# G772B.net
KiCad netlist of a schematic drawn in EAGLE
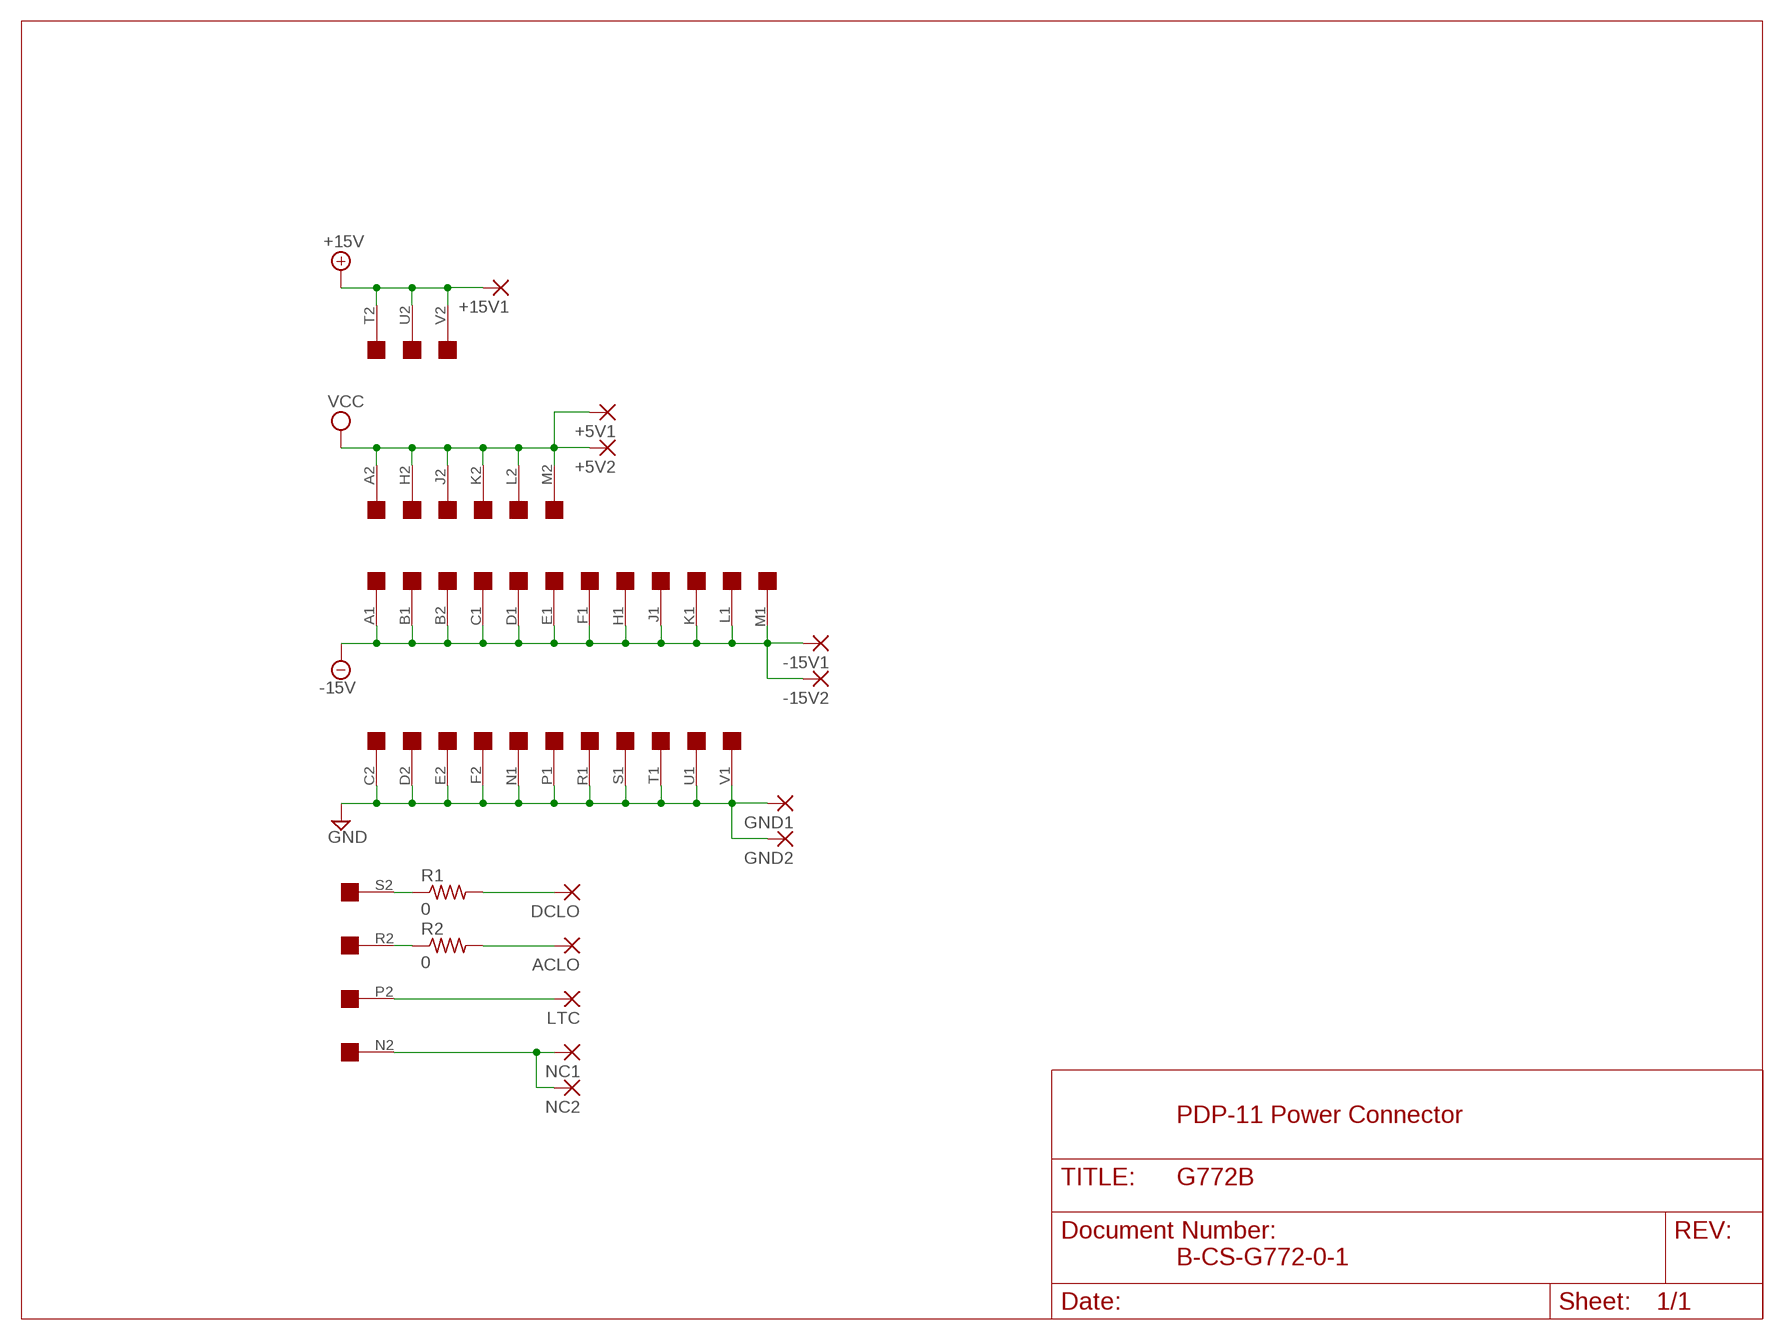
[diagram p0: schematic, sheet 1]

(export (version "E")
  (design (tool "Eeschema 10.0.6"))
  (components
    (comp (ref "+5V1")
      (value "2,54/1,0")
      (footprint "eagle-import:2,54_1,0")
      (libsource (lib "eagle-import") (part "2,54/1,0"))
    )
    (comp (ref "+5V2")
      (value "2,54/1,0")
      (footprint "eagle-import:2,54_1,0")
      (libsource (lib "eagle-import") (part "2,54/1,0"))
    )
    (comp (ref "+15V1")
      (value "2,54/1,0")
      (footprint "eagle-import:2,54_1,0")
      (libsource (lib "eagle-import") (part "2,54/1,0"))
    )
    (comp (ref "-15V1")
      (value "2,54/1,0")
      (footprint "eagle-import:2,54_1,0")
      (libsource (lib "eagle-import") (part "2,54/1,0"))
    )
    (comp (ref "-15V2")
      (value "2,54/1,0")
      (footprint "eagle-import:2,54_1,0")
      (libsource (lib "eagle-import") (part "2,54/1,0"))
    )
    (comp (ref "ACLO")
      (value "2,54/1,0")
      (footprint "eagle-import:2,54_1,0")
      (libsource (lib "eagle-import") (part "2,54/1,0"))
    )
    (comp (ref "DCLO")
      (value "2,54/1,0")
      (footprint "eagle-import:2,54_1,0")
      (libsource (lib "eagle-import") (part "2,54/1,0"))
    )
    (comp (ref "GND1")
      (value "2,54/1,0")
      (footprint "eagle-import:2,54_1,0")
      (libsource (lib "eagle-import") (part "2,54/1,0"))
    )
    (comp (ref "GND2")
      (value "2,54/1,0")
      (footprint "eagle-import:2,54_1,0")
      (libsource (lib "eagle-import") (part "2,54/1,0"))
    )
    (comp (ref "LTC")
      (value "2,54/1,0")
      (footprint "eagle-import:2,54_1,0")
      (libsource (lib "eagle-import") (part "2,54/1,0"))
    )
    (comp (ref "NC1")
      (value "2,54/1,0")
      (footprint "eagle-import:2,54_1,0")
      (libsource (lib "eagle-import") (part "2,54/1,0"))
    )
    (comp (ref "NC2")
      (value "2,54/1,0")
      (footprint "eagle-import:2,54_1,0")
      (libsource (lib "eagle-import") (part "2,54/1,0"))
    )
    (comp (ref "R1")
      (value "0")
      (footprint "eagle-import:0207_10")
      (libsource (lib "eagle-import") (part "R-US_0207/10"))
    )
    (comp (ref "R2")
      (value "0")
      (footprint "eagle-import:0207_10")
      (libsource (lib "eagle-import") (part "R-US_0207/10"))
    )
    (comp (ref "U$1")
      (value "SINGLE")
      (footprint "eagle-import:EDGE-CON2")
      (libsource (lib "eagle-import") (part "SINGLE"))
    )
  )
  (nets
    (net (code "1") (name "+15V") (class "Default")
      (node (ref "+15V1") (pin "1") (pinfunction "P_1") (pintype "passive"))
      (node (ref "U$1") (pin "T2") (pinfunction "1_T2") (pintype "bidirectional"))
      (node (ref "U$1") (pin "U2") (pinfunction "1_U2") (pintype "bidirectional"))
      (node (ref "U$1") (pin "V2") (pinfunction "1_V2") (pintype "bidirectional"))
    )
    (net (code "2") (name "-15V") (class "Default")
      (node (ref "-15V1") (pin "1") (pinfunction "P_1") (pintype "passive"))
      (node (ref "-15V2") (pin "1") (pinfunction "P_1") (pintype "passive"))
      (node (ref "U$1") (pin "A1") (pinfunction "1_A1") (pintype "bidirectional"))
      (node (ref "U$1") (pin "B1") (pinfunction "1_B1") (pintype "bidirectional"))
      (node (ref "U$1") (pin "B2") (pinfunction "1_B2") (pintype "bidirectional"))
      (node (ref "U$1") (pin "C1") (pinfunction "1_C1") (pintype "bidirectional"))
      (node (ref "U$1") (pin "D1") (pinfunction "1_D1") (pintype "bidirectional"))
      (node (ref "U$1") (pin "E1") (pinfunction "1_E1") (pintype "bidirectional"))
      (node (ref "U$1") (pin "F1") (pinfunction "1_F1") (pintype "bidirectional"))
      (node (ref "U$1") (pin "H1") (pinfunction "1_H1") (pintype "bidirectional"))
      (node (ref "U$1") (pin "J1") (pinfunction "1_J1") (pintype "bidirectional"))
      (node (ref "U$1") (pin "K1") (pinfunction "1_K1") (pintype "bidirectional"))
      (node (ref "U$1") (pin "L1") (pinfunction "1_L1") (pintype "bidirectional"))
      (node (ref "U$1") (pin "M1") (pinfunction "1_M1") (pintype "bidirectional"))
    )
    (net (code "3") (name "GND") (class "Default")
      (node (ref "GND1") (pin "1") (pinfunction "P_1") (pintype "passive"))
      (node (ref "GND2") (pin "1") (pinfunction "P_1") (pintype "passive"))
      (node (ref "U$1") (pin "C2") (pinfunction "1_C2") (pintype "bidirectional"))
      (node (ref "U$1") (pin "D2") (pinfunction "1_D2") (pintype "bidirectional"))
      (node (ref "U$1") (pin "E2") (pinfunction "1_E2") (pintype "bidirectional"))
      (node (ref "U$1") (pin "F2") (pinfunction "1_F2") (pintype "bidirectional"))
      (node (ref "U$1") (pin "N1") (pinfunction "1_N1") (pintype "bidirectional"))
      (node (ref "U$1") (pin "P1") (pinfunction "1_P1") (pintype "bidirectional"))
      (node (ref "U$1") (pin "R1") (pinfunction "1_R1") (pintype "bidirectional"))
      (node (ref "U$1") (pin "S1") (pinfunction "1_S1") (pintype "bidirectional"))
      (node (ref "U$1") (pin "T1") (pinfunction "1_T1") (pintype "bidirectional"))
      (node (ref "U$1") (pin "U1") (pinfunction "1_U1") (pintype "bidirectional"))
      (node (ref "U$1") (pin "V1") (pinfunction "1_V1") (pintype "bidirectional"))
    )
    (net (code "4") (name "Net-(ACLO-P)") (class "Default")
      (node (ref "ACLO") (pin "1") (pinfunction "P_1") (pintype "passive"))
      (node (ref "R2") (pin "2") (pinfunction "2_2") (pintype "passive"))
    )
    (net (code "5") (name "Net-(DCLO-P)") (class "Default")
      (node (ref "DCLO") (pin "1") (pinfunction "P_1") (pintype "passive"))
      (node (ref "R1") (pin "2") (pinfunction "2_2") (pintype "passive"))
    )
    (net (code "6") (name "Net-(LTC-P)") (class "Default")
      (node (ref "LTC") (pin "1") (pinfunction "P_1") (pintype "passive"))
      (node (ref "U$1") (pin "P2") (pinfunction "1_P2") (pintype "bidirectional"))
    )
    (net (code "7") (name "Net-(NC1-P)") (class "Default")
      (node (ref "NC1") (pin "1") (pinfunction "P_1") (pintype "passive"))
      (node (ref "NC2") (pin "1") (pinfunction "P_1") (pintype "passive"))
      (node (ref "U$1") (pin "N2") (pinfunction "1_N2") (pintype "bidirectional"))
    )
    (net (code "8") (name "Net-(U$1AB-1)") (class "Default")
      (node (ref "R2") (pin "1") (pinfunction "1_1") (pintype "passive"))
      (node (ref "U$1") (pin "R2") (pinfunction "1_R2") (pintype "bidirectional"))
    )
    (net (code "9") (name "Net-(U$1AD-1)") (class "Default")
      (node (ref "R1") (pin "1") (pinfunction "1_1") (pintype "passive"))
      (node (ref "U$1") (pin "S2") (pinfunction "1_S2") (pintype "bidirectional"))
    )
    (net (code "10") (name "VCC") (class "Default")
      (node (ref "+5V1") (pin "1") (pinfunction "P_1") (pintype "passive"))
      (node (ref "+5V2") (pin "1") (pinfunction "P_1") (pintype "passive"))
      (node (ref "U$1") (pin "A2") (pinfunction "1_A2") (pintype "bidirectional"))
      (node (ref "U$1") (pin "H2") (pinfunction "1_H2") (pintype "bidirectional"))
      (node (ref "U$1") (pin "J2") (pinfunction "1_J2") (pintype "bidirectional"))
      (node (ref "U$1") (pin "K2") (pinfunction "1_K2") (pintype "bidirectional"))
      (node (ref "U$1") (pin "L2") (pinfunction "1_L2") (pintype "bidirectional"))
      (node (ref "U$1") (pin "M2") (pinfunction "1_M2") (pintype "bidirectional"))
    )
  )
)
